# Enclosure_100x68_WS.net
KiCad netlist of a schematic drawn in EAGLE
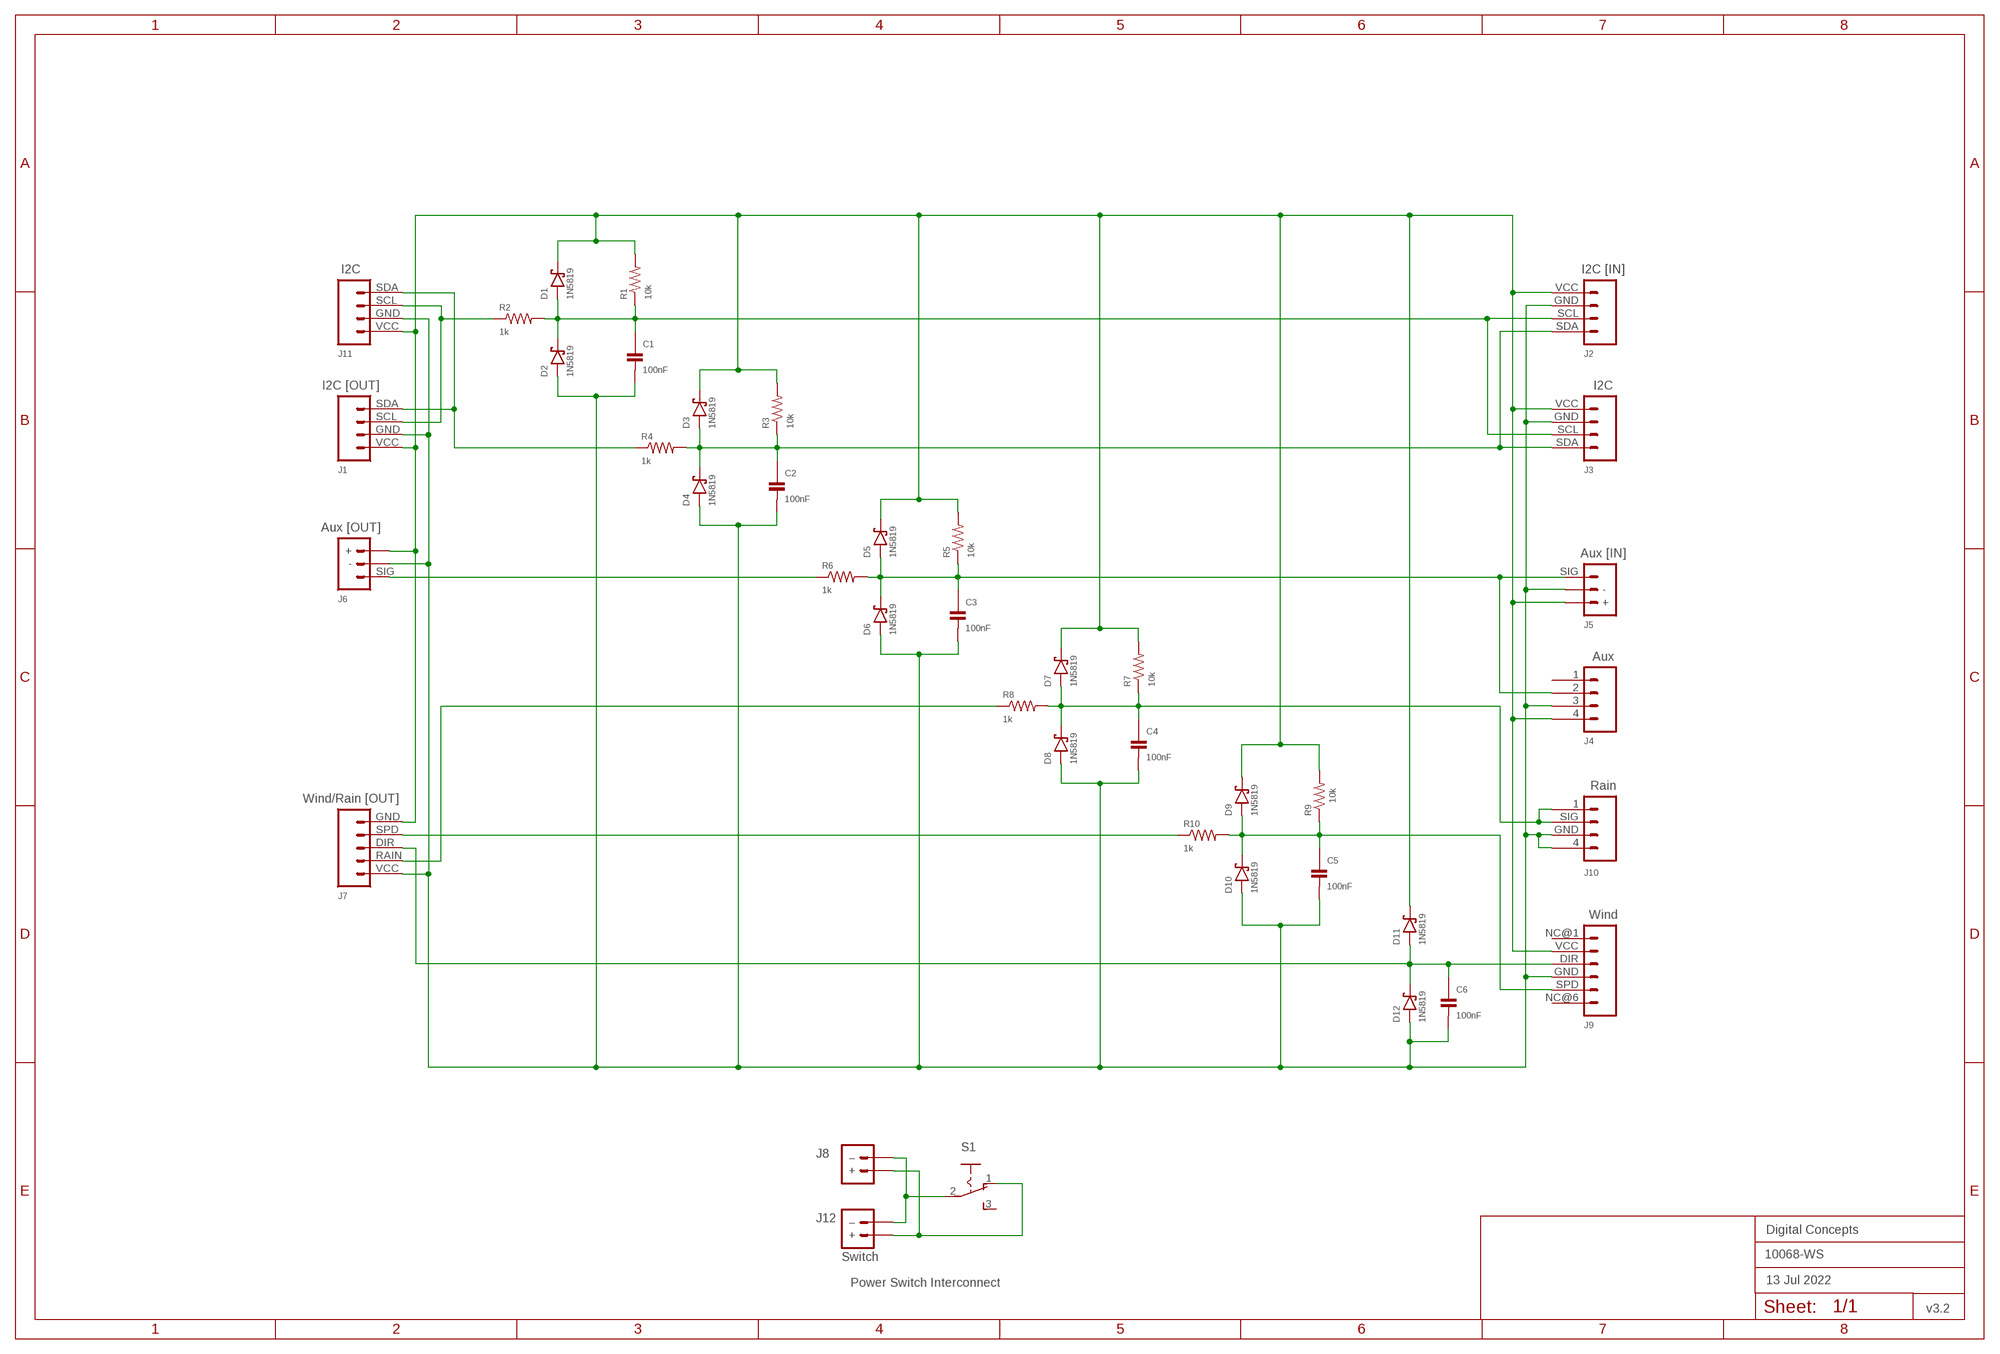
[diagram p0: schematic, sheet 1]

(export (version "E")
  (design (tool "Eeschema 10.0.6"))
  (components
    (comp (ref "C1")
      (value "100nF")
      (footprint "eagle-import:C0805")
      (libsource (lib "eagle-import") (part "CAPACITOR-0805"))
    )
    (comp (ref "C2")
      (value "100nF")
      (footprint "eagle-import:C0805")
      (libsource (lib "eagle-import") (part "CAPACITOR-0805"))
    )
    (comp (ref "C3")
      (value "100nF")
      (footprint "eagle-import:C0805")
      (libsource (lib "eagle-import") (part "CAPACITOR-0805"))
    )
    (comp (ref "C4")
      (value "100nF")
      (footprint "eagle-import:C0805")
      (libsource (lib "eagle-import") (part "CAPACITOR-0805"))
    )
    (comp (ref "C5")
      (value "100nF")
      (footprint "eagle-import:C0805")
      (libsource (lib "eagle-import") (part "CAPACITOR-0805"))
    )
    (comp (ref "C6")
      (value "100nF")
      (footprint "eagle-import:C0805")
      (libsource (lib "eagle-import") (part "CAPACITOR-0805"))
    )
    (comp (ref "D1")
      (value "1N5819")
      (footprint "eagle-import:SOD-123")
      (libsource (lib "eagle-import") (part "DIODE-SCHOTTKY-1N5819"))
    )
    (comp (ref "D2")
      (value "1N5819")
      (footprint "eagle-import:SOD-123")
      (libsource (lib "eagle-import") (part "DIODE-SCHOTTKY-1N5819"))
    )
    (comp (ref "D3")
      (value "1N5819")
      (footprint "eagle-import:SOD-123")
      (libsource (lib "eagle-import") (part "DIODE-SCHOTTKY-1N5819"))
    )
    (comp (ref "D4")
      (value "1N5819")
      (footprint "eagle-import:SOD-123")
      (libsource (lib "eagle-import") (part "DIODE-SCHOTTKY-1N5819"))
    )
    (comp (ref "D5")
      (value "1N5819")
      (footprint "eagle-import:SOD-123")
      (libsource (lib "eagle-import") (part "DIODE-SCHOTTKY-1N5819"))
    )
    (comp (ref "D6")
      (value "1N5819")
      (footprint "eagle-import:SOD-123")
      (libsource (lib "eagle-import") (part "DIODE-SCHOTTKY-1N5819"))
    )
    (comp (ref "D7")
      (value "1N5819")
      (footprint "eagle-import:SOD-123")
      (libsource (lib "eagle-import") (part "DIODE-SCHOTTKY-1N5819"))
    )
    (comp (ref "D8")
      (value "1N5819")
      (footprint "eagle-import:SOD-123")
      (libsource (lib "eagle-import") (part "DIODE-SCHOTTKY-1N5819"))
    )
    (comp (ref "D9")
      (value "1N5819")
      (footprint "eagle-import:SOD-123")
      (libsource (lib "eagle-import") (part "DIODE-SCHOTTKY-1N5819"))
    )
    (comp (ref "D10")
      (value "1N5819")
      (footprint "eagle-import:SOD-123")
      (libsource (lib "eagle-import") (part "DIODE-SCHOTTKY-1N5819"))
    )
    (comp (ref "D11")
      (value "1N5819")
      (footprint "eagle-import:SOD-123")
      (libsource (lib "eagle-import") (part "DIODE-SCHOTTKY-1N5819"))
    )
    (comp (ref "D12")
      (value "1N5819")
      (footprint "eagle-import:SOD-123")
      (libsource (lib "eagle-import") (part "DIODE-SCHOTTKY-1N5819"))
    )
    (comp (ref "J1")
      (value "I2C [OUT]")
      (footprint "eagle-import:JST-PH2.0-4-DUAL-I2C")
      (libsource (lib "eagle-import") (part "JST-PH2.0-4-DUAL-I2C"))
    )
    (comp (ref "J2")
      (value "I2C [IN]")
      (footprint "eagle-import:JST-PH2.0-4-VERTICAL-I2C")
      (libsource (lib "eagle-import") (part "JST-PH2.0-4-VERTICAL-I2C"))
    )
    (comp (ref "J3")
      (value "I2C")
      (footprint "eagle-import:RJ11-4-VERTICAL-I2C")
      (libsource (lib "eagle-import") (part "RJ11-6P4C-VERTICAL-I2C"))
    )
    (comp (ref "J4")
      (value "Aux")
      (footprint "eagle-import:RJ11-4-VERTICAL")
      (libsource (lib "eagle-import") (part "RJ11-6P4C-VERTICAL"))
    )
    (comp (ref "J5")
      (value "Aux [IN]")
      (footprint "eagle-import:JST-PH2.0-3-VERTICAL-SIG")
      (libsource (lib "eagle-import") (part "JST-PH2.0-3-VERTICAL-SIG"))
    )
    (comp (ref "J6")
      (value "Aux [OUT]")
      (footprint "eagle-import:JST-PH2.0-3-DUAL-SIG")
      (libsource (lib "eagle-import") (part "JST-PH2.0-3-DUAL-SIG"))
    )
    (comp (ref "J7")
      (value "Wind/Rain [OUT]")
      (footprint "eagle-import:JST-PH2.0-5-DUAL-WEATHER")
      (libsource (lib "eagle-import") (part "JST-PH2.0-5-DUAL-WEATHER"))
    )
    (comp (ref "J8")
      (value "Switch")
      (footprint "eagle-import:JST-PH2.0-2-VERTICAL=POWER")
      (libsource (lib "eagle-import") (part "JST-PH2.0-2-VERTICAL-POWER"))
    )
    (comp (ref "J9")
      (value "Wind")
      (footprint "eagle-import:RJ11-6-VERTICAL-WIND")
      (libsource (lib "eagle-import") (part "RJ11-6P6C-VERTICAL-WIND"))
    )
    (comp (ref "J10")
      (value "Rain")
      (footprint "eagle-import:RJ11-4-VERTICAL-RAIN")
      (libsource (lib "eagle-import") (part "RJ11-6P4C-VERTICAL-RAIN"))
    )
    (comp (ref "J11")
      (value "I2C")
      (footprint "eagle-import:CONN_04-I2C")
      (libsource (lib "eagle-import") (part "HEADER-1X4-I2C"))
    )
    (comp (ref "J12")
      (value "Switch")
      (footprint "eagle-import:JST-PH2.0-2-HORIZONTAL-POWER")
      (libsource (lib "eagle-import") (part "JST-PH2.0-2-HORIZONTAL-POWERJST-PTH-2"))
    )
    (comp (ref "R1")
      (value "10k")
      (footprint "eagle-import:R0805")
      (libsource (lib "eagle-import") (part "RESISTORR0805"))
    )
    (comp (ref "R2")
      (value "1k")
      (footprint "eagle-import:R0805")
      (libsource (lib "eagle-import") (part "RESISTORR0805"))
    )
    (comp (ref "R3")
      (value "10k")
      (footprint "eagle-import:R0805")
      (libsource (lib "eagle-import") (part "RESISTORR0805"))
    )
    (comp (ref "R4")
      (value "1k")
      (footprint "eagle-import:R0805")
      (libsource (lib "eagle-import") (part "RESISTORR0805"))
    )
    (comp (ref "R5")
      (value "10k")
      (footprint "eagle-import:R0805")
      (libsource (lib "eagle-import") (part "RESISTORR0805"))
    )
    (comp (ref "R6")
      (value "1k")
      (footprint "eagle-import:R0805")
      (libsource (lib "eagle-import") (part "RESISTORR0805"))
    )
    (comp (ref "R7")
      (value "10k")
      (footprint "eagle-import:R0805")
      (libsource (lib "eagle-import") (part "RESISTORR0805"))
    )
    (comp (ref "R8")
      (value "1k")
      (footprint "eagle-import:R0805")
      (libsource (lib "eagle-import") (part "RESISTORR0805"))
    )
    (comp (ref "R9")
      (value "10k")
      (footprint "eagle-import:R0805")
      (libsource (lib "eagle-import") (part "RESISTORR0805"))
    )
    (comp (ref "R10")
      (value "1k")
      (footprint "eagle-import:R0805")
      (libsource (lib "eagle-import") (part "RESISTORR0805"))
    )
    (comp (ref "S1")
      (value "SWITCH-SLIDE-SPDT")
      (footprint "eagle-import:SWITCH-SPDT-PTH")
      (libsource (lib "eagle-import") (part "SWITCH-SLIDE-SPDT"))
    )
  )
  (nets
    (net (code "1") (name "Net-(C3-Pad1)") (class "Default")
      (node (ref "C3") (pin "1") (pinfunction "1_1") (pintype "passive"))
      (node (ref "D5") (pin "A") (pinfunction "A_A") (pintype "passive"))
      (node (ref "D6") (pin "C") (pinfunction "C_C") (pintype "passive"))
      (node (ref "J4") (pin "2") (pinfunction "2_2") (pintype "passive"))
      (node (ref "J5") (pin "SIG") (pinfunction "SIG_SIG") (pintype "bidirectional"))
      (node (ref "R5") (pin "1") (pinfunction "1_1") (pintype "passive"))
      (node (ref "R6") (pin "2") (pinfunction "2_2") (pintype "passive"))
    )
    (net (code "2") (name "Net-(J1-1)") (class "Default")
      (node (ref "D1") (pin "C") (pinfunction "C_C") (pintype "passive"))
      (node (ref "D11") (pin "C") (pinfunction "C_C") (pintype "passive"))
      (node (ref "D3") (pin "C") (pinfunction "C_C") (pintype "passive"))
      (node (ref "D5") (pin "C") (pinfunction "C_C") (pintype "passive"))
      (node (ref "D7") (pin "C") (pinfunction "C_C") (pintype "passive"))
      (node (ref "D9") (pin "C") (pinfunction "C_C") (pintype "passive"))
      (node (ref "J1") (pin "VCC") (pinfunction "1_VCC") (pintype "passive"))
      (node (ref "J11") (pin "VCC") (pinfunction "1_VCC") (pintype "passive"))
      (node (ref "J2") (pin "VCC") (pinfunction "1_VCC") (pintype "passive"))
      (node (ref "J3") (pin "VCC") (pinfunction "1_VCC") (pintype "passive"))
      (node (ref "J4") (pin "4") (pinfunction "4_4") (pintype "passive"))
      (node (ref "J5") (pin "+") (pinfunction "+_+") (pintype "power_in"))
      (node (ref "J6") (pin "+") (pinfunction "+_+") (pintype "power_in"))
      (node (ref "J7") (pin "GND") (pinfunction "5_GND") (pintype "passive"))
      (node (ref "J9") (pin "VCC") (pinfunction "2_VCC") (pintype "passive"))
      (node (ref "R1") (pin "2") (pinfunction "2_2") (pintype "passive"))
      (node (ref "R3") (pin "2") (pinfunction "2_2") (pintype "passive"))
      (node (ref "R5") (pin "2") (pinfunction "2_2") (pintype "passive"))
      (node (ref "R7") (pin "2") (pinfunction "2_2") (pintype "passive"))
      (node (ref "R9") (pin "2") (pinfunction "2_2") (pintype "passive"))
    )
    (net (code "3") (name "Net-(J1-2)") (class "Default")
      (node (ref "C1") (pin "2") (pinfunction "2_2") (pintype "passive"))
      (node (ref "C2") (pin "2") (pinfunction "2_2") (pintype "passive"))
      (node (ref "C3") (pin "2") (pinfunction "2_2") (pintype "passive"))
      (node (ref "C4") (pin "2") (pinfunction "2_2") (pintype "passive"))
      (node (ref "C5") (pin "2") (pinfunction "2_2") (pintype "passive"))
      (node (ref "C6") (pin "2") (pinfunction "2_2") (pintype "passive"))
      (node (ref "D10") (pin "A") (pinfunction "A_A") (pintype "passive"))
      (node (ref "D12") (pin "A") (pinfunction "A_A") (pintype "passive"))
      (node (ref "D2") (pin "A") (pinfunction "A_A") (pintype "passive"))
      (node (ref "D4") (pin "A") (pinfunction "A_A") (pintype "passive"))
      (node (ref "D6") (pin "A") (pinfunction "A_A") (pintype "passive"))
      (node (ref "D8") (pin "A") (pinfunction "A_A") (pintype "passive"))
      (node (ref "J1") (pin "GND") (pinfunction "2_GND") (pintype "passive"))
      (node (ref "J10") (pin "4") (pinfunction "4_4") (pintype "passive"))
      (node (ref "J10") (pin "GND") (pinfunction "3_GND") (pintype "passive"))
      (node (ref "J11") (pin "GND") (pinfunction "2_GND") (pintype "passive"))
      (node (ref "J2") (pin "GND") (pinfunction "2_GND") (pintype "passive"))
      (node (ref "J3") (pin "GND") (pinfunction "2_GND") (pintype "passive"))
      (node (ref "J4") (pin "3") (pinfunction "3_3") (pintype "passive"))
      (node (ref "J5") (pin "-") (pinfunction "-_-") (pintype "power_in"))
      (node (ref "J6") (pin "-") (pinfunction "-_-") (pintype "power_in"))
      (node (ref "J7") (pin "VCC") (pinfunction "1_VCC") (pintype "passive"))
      (node (ref "J9") (pin "GND") (pinfunction "4_GND") (pintype "passive"))
    )
    (net (code "4") (name "Net-(J1-3)") (class "Default")
      (node (ref "J1") (pin "SCL") (pinfunction "3_SCL") (pintype "passive"))
      (node (ref "J11") (pin "SCL") (pinfunction "3_SCL") (pintype "passive"))
      (node (ref "R2") (pin "1") (pinfunction "1_1") (pintype "passive"))
    )
    (net (code "5") (name "Net-(J1-4)") (class "Default")
      (node (ref "J1") (pin "SDA") (pinfunction "4_SDA") (pintype "passive"))
      (node (ref "J11") (pin "SDA") (pinfunction "4_SDA") (pintype "passive"))
      (node (ref "R4") (pin "1") (pinfunction "1_1") (pintype "passive"))
    )
    (net (code "6") (name "Net-(J2-3)") (class "Default")
      (node (ref "C1") (pin "1") (pinfunction "1_1") (pintype "passive"))
      (node (ref "D1") (pin "A") (pinfunction "A_A") (pintype "passive"))
      (node (ref "D2") (pin "C") (pinfunction "C_C") (pintype "passive"))
      (node (ref "J2") (pin "SCL") (pinfunction "3_SCL") (pintype "passive"))
      (node (ref "J3") (pin "SCL") (pinfunction "3_SCL") (pintype "passive"))
      (node (ref "R1") (pin "1") (pinfunction "1_1") (pintype "passive"))
      (node (ref "R2") (pin "2") (pinfunction "2_2") (pintype "passive"))
    )
    (net (code "7") (name "Net-(J2-4)") (class "Default")
      (node (ref "C2") (pin "1") (pinfunction "1_1") (pintype "passive"))
      (node (ref "D3") (pin "A") (pinfunction "A_A") (pintype "passive"))
      (node (ref "D4") (pin "C") (pinfunction "C_C") (pintype "passive"))
      (node (ref "J2") (pin "SDA") (pinfunction "4_SDA") (pintype "passive"))
      (node (ref "J3") (pin "SDA") (pinfunction "4_SDA") (pintype "passive"))
      (node (ref "R3") (pin "1") (pinfunction "1_1") (pintype "passive"))
      (node (ref "R4") (pin "2") (pinfunction "2_2") (pintype "passive"))
    )
    (net (code "8") (name "Net-(J6-PadSIG)") (class "Default")
      (node (ref "J6") (pin "SIG") (pinfunction "SIG_SIG") (pintype "bidirectional"))
      (node (ref "R6") (pin "1") (pinfunction "1_1") (pintype "passive"))
    )
    (net (code "9") (name "Net-(J7-2)") (class "Default")
      (node (ref "J7") (pin "RAIN") (pinfunction "2_RAIN") (pintype "passive"))
      (node (ref "R8") (pin "1") (pinfunction "1_1") (pintype "passive"))
    )
    (net (code "10") (name "Net-(J7-3)") (class "Default")
      (node (ref "C6") (pin "1") (pinfunction "1_1") (pintype "passive"))
      (node (ref "D11") (pin "A") (pinfunction "A_A") (pintype "passive"))
      (node (ref "D12") (pin "C") (pinfunction "C_C") (pintype "passive"))
      (node (ref "J7") (pin "DIR") (pinfunction "3_DIR") (pintype "passive"))
      (node (ref "J9") (pin "DIR") (pinfunction "3_DIR") (pintype "passive"))
    )
    (net (code "11") (name "Net-(J7-4)") (class "Default")
      (node (ref "J7") (pin "SPD") (pinfunction "4_SPD") (pintype "passive"))
      (node (ref "R10") (pin "1") (pinfunction "1_1") (pintype "passive"))
    )
    (net (code "12") (name "Net-(J9-5)") (class "Default")
      (node (ref "C5") (pin "1") (pinfunction "1_1") (pintype "passive"))
      (node (ref "D10") (pin "C") (pinfunction "C_C") (pintype "passive"))
      (node (ref "D9") (pin "A") (pinfunction "A_A") (pintype "passive"))
      (node (ref "J9") (pin "SPD") (pinfunction "5_SPD") (pintype "passive"))
      (node (ref "R10") (pin "2") (pinfunction "2_2") (pintype "passive"))
      (node (ref "R9") (pin "1") (pinfunction "1_1") (pintype "passive"))
    )
    (net (code "13") (name "Net-(J10-2)") (class "Default")
      (node (ref "C4") (pin "1") (pinfunction "1_1") (pintype "passive"))
      (node (ref "D7") (pin "A") (pinfunction "A_A") (pintype "passive"))
      (node (ref "D8") (pin "C") (pinfunction "C_C") (pintype "passive"))
      (node (ref "J10") (pin "1") (pinfunction "1_1") (pintype "passive"))
      (node (ref "J10") (pin "SIG") (pinfunction "2_SIG") (pintype "passive"))
      (node (ref "R7") (pin "1") (pinfunction "1_1") (pintype "passive"))
      (node (ref "R8") (pin "2") (pinfunction "2_2") (pintype "passive"))
    )
    (net (code "14") (name "Net-(J12-–)") (class "Default")
      (node (ref "J12") (pin "-") (pinfunction "–_-") (pintype "power_in"))
      (node (ref "J8") (pin "-") (pinfunction "–_-") (pintype "power_in"))
      (node (ref "S1") (pin "2") (pinfunction "P_2") (pintype "passive"))
    )
    (net (code "15") (name "Net-(S1-O)") (class "Default")
      (node (ref "J12") (pin "+") (pinfunction "+_+") (pintype "power_in"))
      (node (ref "J8") (pin "+") (pinfunction "+_+") (pintype "power_in"))
      (node (ref "S1") (pin "1") (pinfunction "O_1") (pintype "passive"))
    )
    (net (code "16") (name "unconnected-(J4-Pad1)") (class "Default")
      (node (ref "J4") (pin "1") (pinfunction "1_1") (pintype "passive"))
    )
    (net (code "17") (name "unconnected-(J9-1-PadNC@1)") (class "Default")
      (node (ref "J9") (pin "NC@1") (pinfunction "1_NC@1") (pintype "passive"))
    )
    (net (code "18") (name "unconnected-(J9-6-PadNC@6)") (class "Default")
      (node (ref "J9") (pin "NC@6") (pinfunction "6_NC@6") (pintype "passive"))
    )
    (net (code "19") (name "unconnected-(S1-S-Pad3)") (class "Default")
      (node (ref "S1") (pin "3") (pinfunction "S_3") (pintype "passive"))
    )
  )
)
